# Chov2_led.net
KiCad netlist of a schematic drawn in Altium Designer
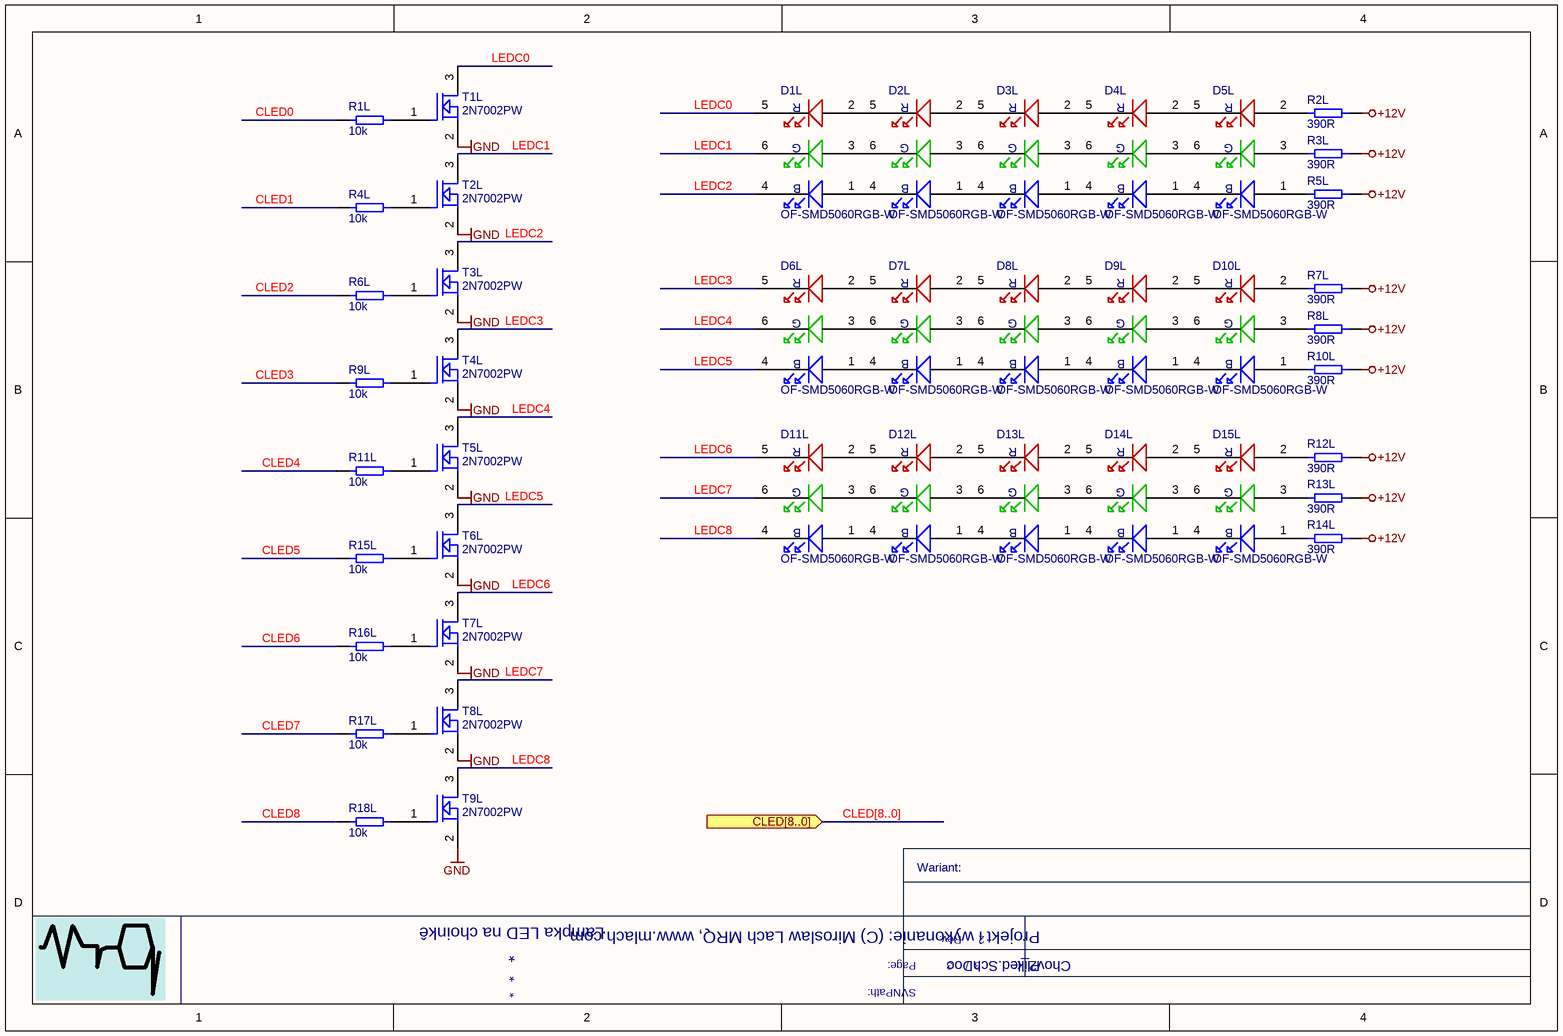
[diagram p0: Chov2_led.SchDoc]

(export (version "E")
  (design (tool "Eeschema 10.0.6"))
  (components
    (comp (ref "D1L")
      (value "OF-SMD5060RGB-W")
      (footprint "OF-SMD5060RGB-W")
      (libsource (lib "Parts") (part "OF-SMD5060RGB-W"))
    )
    (comp (ref "D2L")
      (value "OF-SMD5060RGB-W")
      (footprint "OF-SMD5060RGB-W")
      (libsource (lib "Parts") (part "OF-SMD5060RGB-W"))
    )
    (comp (ref "D3L")
      (value "OF-SMD5060RGB-W")
      (footprint "OF-SMD5060RGB-W")
      (libsource (lib "Parts") (part "OF-SMD5060RGB-W"))
    )
    (comp (ref "D4L")
      (value "OF-SMD5060RGB-W")
      (footprint "OF-SMD5060RGB-W")
      (libsource (lib "Parts") (part "OF-SMD5060RGB-W"))
    )
    (comp (ref "D5L")
      (value "OF-SMD5060RGB-W")
      (footprint "OF-SMD5060RGB-W")
      (libsource (lib "Parts") (part "OF-SMD5060RGB-W"))
    )
    (comp (ref "D6L")
      (value "OF-SMD5060RGB-W")
      (footprint "OF-SMD5060RGB-W")
      (libsource (lib "Parts") (part "OF-SMD5060RGB-W"))
    )
    (comp (ref "D7L")
      (value "OF-SMD5060RGB-W")
      (footprint "OF-SMD5060RGB-W")
      (libsource (lib "Parts") (part "OF-SMD5060RGB-W"))
    )
    (comp (ref "D8L")
      (value "OF-SMD5060RGB-W")
      (footprint "OF-SMD5060RGB-W")
      (libsource (lib "Parts") (part "OF-SMD5060RGB-W"))
    )
    (comp (ref "D9L")
      (value "OF-SMD5060RGB-W")
      (footprint "OF-SMD5060RGB-W")
      (libsource (lib "Parts") (part "OF-SMD5060RGB-W"))
    )
    (comp (ref "D10L")
      (value "OF-SMD5060RGB-W")
      (footprint "OF-SMD5060RGB-W")
      (libsource (lib "Parts") (part "OF-SMD5060RGB-W"))
    )
    (comp (ref "D11L")
      (value "OF-SMD5060RGB-W")
      (footprint "OF-SMD5060RGB-W")
      (libsource (lib "Parts") (part "OF-SMD5060RGB-W"))
    )
    (comp (ref "D12L")
      (value "OF-SMD5060RGB-W")
      (footprint "OF-SMD5060RGB-W")
      (libsource (lib "Parts") (part "OF-SMD5060RGB-W"))
    )
    (comp (ref "D13L")
      (value "OF-SMD5060RGB-W")
      (footprint "OF-SMD5060RGB-W")
      (libsource (lib "Parts") (part "OF-SMD5060RGB-W"))
    )
    (comp (ref "D14L")
      (value "OF-SMD5060RGB-W")
      (footprint "OF-SMD5060RGB-W")
      (libsource (lib "Parts") (part "OF-SMD5060RGB-W"))
    )
    (comp (ref "D15L")
      (value "OF-SMD5060RGB-W")
      (footprint "OF-SMD5060RGB-W")
      (libsource (lib "Parts") (part "OF-SMD5060RGB-W"))
    )
    (comp (ref "R1L")
      (value "0603WGF10KT5E")
      (footprint "0603-IPC")
      (fields (field (name "OTHERPARAMS") "10k") (field (name "TOLERANCE") "1%"))
      (libsource (lib "Parts") (part "R"))
    )
    (comp (ref "R2L")
      (value "0805WAF 390R T5E")
      (footprint "0805")
      (fields (field (name "OTHERPARAMS") "390R") (field (name "TOLERANCE") "1%"))
      (libsource (lib "Parts") (part "R"))
    )
    (comp (ref "R3L")
      (value "0805WAF 390R T5E")
      (footprint "0805")
      (fields (field (name "OTHERPARAMS") "390R") (field (name "TOLERANCE") "1%"))
      (libsource (lib "Parts") (part "R"))
    )
    (comp (ref "R4L")
      (value "0603WGF10KT5E")
      (footprint "0603-IPC")
      (fields (field (name "OTHERPARAMS") "10k") (field (name "TOLERANCE") "1%"))
      (libsource (lib "Parts") (part "R"))
    )
    (comp (ref "R5L")
      (value "0805WAF 390R T5E")
      (footprint "0805")
      (fields (field (name "OTHERPARAMS") "390R") (field (name "TOLERANCE") "1%"))
      (libsource (lib "Parts") (part "R"))
    )
    (comp (ref "R6L")
      (value "0603WGF10KT5E")
      (footprint "0603-IPC")
      (fields (field (name "OTHERPARAMS") "10k") (field (name "TOLERANCE") "1%"))
      (libsource (lib "Parts") (part "R"))
    )
    (comp (ref "R7L")
      (value "0805WAF 390R T5E")
      (footprint "0805")
      (fields (field (name "OTHERPARAMS") "390R") (field (name "TOLERANCE") "1%"))
      (libsource (lib "Parts") (part "R"))
    )
    (comp (ref "R8L")
      (value "0805WAF 390R T5E")
      (footprint "0805")
      (fields (field (name "OTHERPARAMS") "390R") (field (name "TOLERANCE") "1%"))
      (libsource (lib "Parts") (part "R"))
    )
    (comp (ref "R9L")
      (value "0603WGF10KT5E")
      (footprint "0603-IPC")
      (fields (field (name "OTHERPARAMS") "10k") (field (name "TOLERANCE") "1%"))
      (libsource (lib "Parts") (part "R"))
    )
    (comp (ref "R10L")
      (value "0805WAF 390R T5E")
      (footprint "0805")
      (fields (field (name "OTHERPARAMS") "390R") (field (name "TOLERANCE") "1%"))
      (libsource (lib "Parts") (part "R"))
    )
    (comp (ref "R11L")
      (value "0603WGF10KT5E")
      (footprint "0603-IPC")
      (fields (field (name "OTHERPARAMS") "10k") (field (name "TOLERANCE") "1%"))
      (libsource (lib "Parts") (part "R"))
    )
    (comp (ref "R12L")
      (value "0805WAF 390R T5E")
      (footprint "0805")
      (fields (field (name "OTHERPARAMS") "390R") (field (name "TOLERANCE") "1%"))
      (libsource (lib "Parts") (part "R"))
    )
    (comp (ref "R13L")
      (value "0805WAF 390R T5E")
      (footprint "0805")
      (fields (field (name "OTHERPARAMS") "390R") (field (name "TOLERANCE") "1%"))
      (libsource (lib "Parts") (part "R"))
    )
    (comp (ref "R14L")
      (value "0805WAF 390R T5E")
      (footprint "0805")
      (fields (field (name "OTHERPARAMS") "390R") (field (name "TOLERANCE") "1%"))
      (libsource (lib "Parts") (part "R"))
    )
    (comp (ref "R15L")
      (value "0603WGF10KT5E")
      (footprint "0603-IPC")
      (fields (field (name "OTHERPARAMS") "10k") (field (name "TOLERANCE") "1%"))
      (libsource (lib "Parts") (part "R"))
    )
    (comp (ref "R16L")
      (value "0603WGF10KT5E")
      (footprint "0603-IPC")
      (fields (field (name "OTHERPARAMS") "10k") (field (name "TOLERANCE") "1%"))
      (libsource (lib "Parts") (part "R"))
    )
    (comp (ref "R17L")
      (value "0603WGF10KT5E")
      (footprint "0603-IPC")
      (fields (field (name "OTHERPARAMS") "10k") (field (name "TOLERANCE") "1%"))
      (libsource (lib "Parts") (part "R"))
    )
    (comp (ref "R18L")
      (value "0603WGF10KT5E")
      (footprint "0603-IPC")
      (fields (field (name "OTHERPARAMS") "10k") (field (name "TOLERANCE") "1%"))
      (libsource (lib "Parts") (part "R"))
    )
    (comp (ref "T1L")
      (value "2N7002PW")
      (footprint "SOT323-3_FLOW")
      (libsource (lib "Parts") (part "MOSFET_N_SOT23-3"))
    )
    (comp (ref "T2L")
      (value "2N7002PW")
      (footprint "SOT323-3_FLOW")
      (libsource (lib "Parts") (part "MOSFET_N_SOT23-3"))
    )
    (comp (ref "T3L")
      (value "2N7002PW")
      (footprint "SOT323-3_FLOW")
      (libsource (lib "Parts") (part "MOSFET_N_SOT23-3"))
    )
    (comp (ref "T4L")
      (value "2N7002PW")
      (footprint "SOT323-3_FLOW")
      (libsource (lib "Parts") (part "MOSFET_N_SOT23-3"))
    )
    (comp (ref "T5L")
      (value "2N7002PW")
      (footprint "SOT323-3_FLOW")
      (libsource (lib "Parts") (part "MOSFET_N_SOT23-3"))
    )
    (comp (ref "T6L")
      (value "2N7002PW")
      (footprint "SOT323-3_FLOW")
      (libsource (lib "Parts") (part "MOSFET_N_SOT23-3"))
    )
    (comp (ref "T7L")
      (value "2N7002PW")
      (footprint "SOT323-3_FLOW")
      (libsource (lib "Parts") (part "MOSFET_N_SOT23-3"))
    )
    (comp (ref "T8L")
      (value "2N7002PW")
      (footprint "SOT323-3_FLOW")
      (libsource (lib "Parts") (part "MOSFET_N_SOT23-3"))
    )
    (comp (ref "T9L")
      (value "2N7002PW")
      (footprint "SOT323-3_FLOW")
      (libsource (lib "Parts") (part "MOSFET_N_SOT23-3"))
    )
  )
  (nets
    (net (code "1") (name "+12V") (class "Default")
      (node (ref "R10L") (pin "2") (pinfunction "2_2") (pintype "passive"))
      (node (ref "R12L") (pin "2") (pinfunction "2_2") (pintype "passive"))
      (node (ref "R13L") (pin "2") (pinfunction "2_2") (pintype "passive"))
      (node (ref "R14L") (pin "2") (pinfunction "2_2") (pintype "passive"))
      (node (ref "R2L") (pin "2") (pinfunction "2_2") (pintype "passive"))
      (node (ref "R3L") (pin "2") (pinfunction "2_2") (pintype "passive"))
      (node (ref "R5L") (pin "2") (pinfunction "2_2") (pintype "passive"))
      (node (ref "R7L") (pin "2") (pinfunction "2_2") (pintype "passive"))
      (node (ref "R8L") (pin "2") (pinfunction "2_2") (pintype "passive"))
    )
    (net (code "2") (name "/CLED0") (class "Default")
      (node (ref "R1L") (pin "1") (pinfunction "1_1") (pintype "passive"))
    )
    (net (code "3") (name "/CLED1") (class "Default")
      (node (ref "R4L") (pin "1") (pinfunction "1_1") (pintype "passive"))
    )
    (net (code "4") (name "/CLED2") (class "Default")
      (node (ref "R6L") (pin "1") (pinfunction "1_1") (pintype "passive"))
    )
    (net (code "5") (name "/CLED3") (class "Default")
      (node (ref "R9L") (pin "1") (pinfunction "1_1") (pintype "passive"))
    )
    (net (code "6") (name "/CLED4") (class "Default")
      (node (ref "R11L") (pin "1") (pinfunction "1_1") (pintype "passive"))
    )
    (net (code "7") (name "/CLED5") (class "Default")
      (node (ref "R15L") (pin "1") (pinfunction "1_1") (pintype "passive"))
    )
    (net (code "8") (name "/CLED6") (class "Default")
      (node (ref "R16L") (pin "1") (pinfunction "1_1") (pintype "passive"))
    )
    (net (code "9") (name "/CLED7") (class "Default")
      (node (ref "R17L") (pin "1") (pinfunction "1_1") (pintype "passive"))
    )
    (net (code "10") (name "/CLED8") (class "Default")
      (node (ref "R18L") (pin "1") (pinfunction "1_1") (pintype "passive"))
    )
    (net (code "12") (name "/LEDC0") (class "Default")
      (node (ref "D1L") (pin "5") (pinfunction "CATH_5") (pintype "passive"))
      (node (ref "T1L") (pin "3") (pinfunction "DRAIN_3") (pintype "passive"))
    )
    (net (code "13") (name "/LEDC1") (class "Default")
      (node (ref "D1L") (pin "6") (pinfunction "CATH_6") (pintype "passive"))
      (node (ref "T2L") (pin "3") (pinfunction "DRAIN_3") (pintype "passive"))
    )
    (net (code "14") (name "/LEDC2") (class "Default")
      (node (ref "D1L") (pin "4") (pinfunction "CATH_4") (pintype "passive"))
      (node (ref "T3L") (pin "3") (pinfunction "DRAIN_3") (pintype "passive"))
    )
    (net (code "15") (name "/LEDC3") (class "Default")
      (node (ref "D6L") (pin "5") (pinfunction "CATH_5") (pintype "passive"))
      (node (ref "T4L") (pin "3") (pinfunction "DRAIN_3") (pintype "passive"))
    )
    (net (code "16") (name "/LEDC4") (class "Default")
      (node (ref "D6L") (pin "6") (pinfunction "CATH_6") (pintype "passive"))
      (node (ref "T5L") (pin "3") (pinfunction "DRAIN_3") (pintype "passive"))
    )
    (net (code "17") (name "/LEDC5") (class "Default")
      (node (ref "D6L") (pin "4") (pinfunction "CATH_4") (pintype "passive"))
      (node (ref "T6L") (pin "3") (pinfunction "DRAIN_3") (pintype "passive"))
    )
    (net (code "18") (name "/LEDC6") (class "Default")
      (node (ref "D11L") (pin "5") (pinfunction "CATH_5") (pintype "passive"))
      (node (ref "T7L") (pin "3") (pinfunction "DRAIN_3") (pintype "passive"))
    )
    (net (code "19") (name "/LEDC7") (class "Default")
      (node (ref "D11L") (pin "6") (pinfunction "CATH_6") (pintype "passive"))
      (node (ref "T8L") (pin "3") (pinfunction "DRAIN_3") (pintype "passive"))
    )
    (net (code "20") (name "/LEDC8") (class "Default")
      (node (ref "D11L") (pin "4") (pinfunction "CATH_4") (pintype "passive"))
      (node (ref "T9L") (pin "3") (pinfunction "DRAIN_3") (pintype "passive"))
    )
    (net (code "21") (name "GND") (class "Default")
      (node (ref "T1L") (pin "2") (pinfunction "SOURCE_2") (pintype "passive"))
      (node (ref "T2L") (pin "2") (pinfunction "SOURCE_2") (pintype "passive"))
      (node (ref "T3L") (pin "2") (pinfunction "SOURCE_2") (pintype "passive"))
      (node (ref "T4L") (pin "2") (pinfunction "SOURCE_2") (pintype "passive"))
      (node (ref "T5L") (pin "2") (pinfunction "SOURCE_2") (pintype "passive"))
      (node (ref "T6L") (pin "2") (pinfunction "SOURCE_2") (pintype "passive"))
      (node (ref "T7L") (pin "2") (pinfunction "SOURCE_2") (pintype "passive"))
      (node (ref "T8L") (pin "2") (pinfunction "SOURCE_2") (pintype "passive"))
      (node (ref "T9L") (pin "2") (pinfunction "SOURCE_2") (pintype "passive"))
    )
    (net (code "22") (name "Net-(D1L-ANOD-Pad1)") (class "Default")
      (node (ref "D1L") (pin "1") (pinfunction "ANOD_1") (pintype "passive"))
      (node (ref "D2L") (pin "4") (pinfunction "CATH_4") (pintype "passive"))
    )
    (net (code "23") (name "Net-(D1L-ANOD-Pad2)") (class "Default")
      (node (ref "D1L") (pin "2") (pinfunction "ANOD_2") (pintype "passive"))
      (node (ref "D2L") (pin "5") (pinfunction "CATH_5") (pintype "passive"))
    )
    (net (code "24") (name "Net-(D1L-ANOD-Pad3)") (class "Default")
      (node (ref "D1L") (pin "3") (pinfunction "ANOD_3") (pintype "passive"))
      (node (ref "D2L") (pin "6") (pinfunction "CATH_6") (pintype "passive"))
    )
    (net (code "25") (name "Net-(D2L-ANOD-Pad1)") (class "Default")
      (node (ref "D2L") (pin "1") (pinfunction "ANOD_1") (pintype "passive"))
      (node (ref "D3L") (pin "4") (pinfunction "CATH_4") (pintype "passive"))
    )
    (net (code "26") (name "Net-(D2L-ANOD-Pad2)") (class "Default")
      (node (ref "D2L") (pin "2") (pinfunction "ANOD_2") (pintype "passive"))
      (node (ref "D3L") (pin "5") (pinfunction "CATH_5") (pintype "passive"))
    )
    (net (code "27") (name "Net-(D2L-ANOD-Pad3)") (class "Default")
      (node (ref "D2L") (pin "3") (pinfunction "ANOD_3") (pintype "passive"))
      (node (ref "D3L") (pin "6") (pinfunction "CATH_6") (pintype "passive"))
    )
    (net (code "28") (name "Net-(D3L-ANOD-Pad1)") (class "Default")
      (node (ref "D3L") (pin "1") (pinfunction "ANOD_1") (pintype "passive"))
      (node (ref "D4L") (pin "4") (pinfunction "CATH_4") (pintype "passive"))
    )
    (net (code "29") (name "Net-(D3L-ANOD-Pad2)") (class "Default")
      (node (ref "D3L") (pin "2") (pinfunction "ANOD_2") (pintype "passive"))
      (node (ref "D4L") (pin "5") (pinfunction "CATH_5") (pintype "passive"))
    )
    (net (code "30") (name "Net-(D3L-ANOD-Pad3)") (class "Default")
      (node (ref "D3L") (pin "3") (pinfunction "ANOD_3") (pintype "passive"))
      (node (ref "D4L") (pin "6") (pinfunction "CATH_6") (pintype "passive"))
    )
    (net (code "31") (name "Net-(D4L-ANOD-Pad1)") (class "Default")
      (node (ref "D4L") (pin "1") (pinfunction "ANOD_1") (pintype "passive"))
      (node (ref "D5L") (pin "4") (pinfunction "CATH_4") (pintype "passive"))
    )
    (net (code "32") (name "Net-(D4L-ANOD-Pad2)") (class "Default")
      (node (ref "D4L") (pin "2") (pinfunction "ANOD_2") (pintype "passive"))
      (node (ref "D5L") (pin "5") (pinfunction "CATH_5") (pintype "passive"))
    )
    (net (code "33") (name "Net-(D4L-ANOD-Pad3)") (class "Default")
      (node (ref "D4L") (pin "3") (pinfunction "ANOD_3") (pintype "passive"))
      (node (ref "D5L") (pin "6") (pinfunction "CATH_6") (pintype "passive"))
    )
    (net (code "34") (name "Net-(D5L-ANOD-Pad1)") (class "Default")
      (node (ref "D5L") (pin "1") (pinfunction "ANOD_1") (pintype "passive"))
      (node (ref "R5L") (pin "1") (pinfunction "1_1") (pintype "passive"))
    )
    (net (code "35") (name "Net-(D5L-ANOD-Pad2)") (class "Default")
      (node (ref "D5L") (pin "2") (pinfunction "ANOD_2") (pintype "passive"))
      (node (ref "R2L") (pin "1") (pinfunction "1_1") (pintype "passive"))
    )
    (net (code "36") (name "Net-(D5L-ANOD-Pad3)") (class "Default")
      (node (ref "D5L") (pin "3") (pinfunction "ANOD_3") (pintype "passive"))
      (node (ref "R3L") (pin "1") (pinfunction "1_1") (pintype "passive"))
    )
    (net (code "37") (name "Net-(D6L-ANOD-Pad1)") (class "Default")
      (node (ref "D6L") (pin "1") (pinfunction "ANOD_1") (pintype "passive"))
      (node (ref "D7L") (pin "4") (pinfunction "CATH_4") (pintype "passive"))
    )
    (net (code "38") (name "Net-(D6L-ANOD-Pad2)") (class "Default")
      (node (ref "D6L") (pin "2") (pinfunction "ANOD_2") (pintype "passive"))
      (node (ref "D7L") (pin "5") (pinfunction "CATH_5") (pintype "passive"))
    )
    (net (code "39") (name "Net-(D6L-ANOD-Pad3)") (class "Default")
      (node (ref "D6L") (pin "3") (pinfunction "ANOD_3") (pintype "passive"))
      (node (ref "D7L") (pin "6") (pinfunction "CATH_6") (pintype "passive"))
    )
    (net (code "40") (name "Net-(D7L-ANOD-Pad1)") (class "Default")
      (node (ref "D7L") (pin "1") (pinfunction "ANOD_1") (pintype "passive"))
      (node (ref "D8L") (pin "4") (pinfunction "CATH_4") (pintype "passive"))
    )
    (net (code "41") (name "Net-(D7L-ANOD-Pad2)") (class "Default")
      (node (ref "D7L") (pin "2") (pinfunction "ANOD_2") (pintype "passive"))
      (node (ref "D8L") (pin "5") (pinfunction "CATH_5") (pintype "passive"))
    )
    (net (code "42") (name "Net-(D7L-ANOD-Pad3)") (class "Default")
      (node (ref "D7L") (pin "3") (pinfunction "ANOD_3") (pintype "passive"))
      (node (ref "D8L") (pin "6") (pinfunction "CATH_6") (pintype "passive"))
    )
    (net (code "43") (name "Net-(D8L-ANOD-Pad1)") (class "Default")
      (node (ref "D8L") (pin "1") (pinfunction "ANOD_1") (pintype "passive"))
      (node (ref "D9L") (pin "4") (pinfunction "CATH_4") (pintype "passive"))
    )
    (net (code "44") (name "Net-(D8L-ANOD-Pad2)") (class "Default")
      (node (ref "D8L") (pin "2") (pinfunction "ANOD_2") (pintype "passive"))
      (node (ref "D9L") (pin "5") (pinfunction "CATH_5") (pintype "passive"))
    )
    (net (code "45") (name "Net-(D8L-ANOD-Pad3)") (class "Default")
      (node (ref "D8L") (pin "3") (pinfunction "ANOD_3") (pintype "passive"))
      (node (ref "D9L") (pin "6") (pinfunction "CATH_6") (pintype "passive"))
    )
    (net (code "46") (name "Net-(D10L-ANOD-Pad1)") (class "Default")
      (node (ref "D10L") (pin "1") (pinfunction "ANOD_1") (pintype "passive"))
      (node (ref "R10L") (pin "1") (pinfunction "1_1") (pintype "passive"))
    )
    (net (code "47") (name "Net-(D10L-ANOD-Pad2)") (class "Default")
      (node (ref "D10L") (pin "2") (pinfunction "ANOD_2") (pintype "passive"))
      (node (ref "R7L") (pin "1") (pinfunction "1_1") (pintype "passive"))
    )
    (net (code "48") (name "Net-(D10L-ANOD-Pad3)") (class "Default")
      (node (ref "D10L") (pin "3") (pinfunction "ANOD_3") (pintype "passive"))
      (node (ref "R8L") (pin "1") (pinfunction "1_1") (pintype "passive"))
    )
    (net (code "49") (name "Net-(D10L-CATH-Pad4)") (class "Default")
      (node (ref "D10L") (pin "4") (pinfunction "CATH_4") (pintype "passive"))
      (node (ref "D9L") (pin "1") (pinfunction "ANOD_1") (pintype "passive"))
    )
    (net (code "50") (name "Net-(D10L-CATH-Pad5)") (class "Default")
      (node (ref "D10L") (pin "5") (pinfunction "CATH_5") (pintype "passive"))
      (node (ref "D9L") (pin "2") (pinfunction "ANOD_2") (pintype "passive"))
    )
    (net (code "51") (name "Net-(D10L-CATH-Pad6)") (class "Default")
      (node (ref "D10L") (pin "6") (pinfunction "CATH_6") (pintype "passive"))
      (node (ref "D9L") (pin "3") (pinfunction "ANOD_3") (pintype "passive"))
    )
    (net (code "52") (name "Net-(D11L-ANOD-Pad1)") (class "Default")
      (node (ref "D11L") (pin "1") (pinfunction "ANOD_1") (pintype "passive"))
      (node (ref "D12L") (pin "4") (pinfunction "CATH_4") (pintype "passive"))
    )
    (net (code "53") (name "Net-(D11L-ANOD-Pad2)") (class "Default")
      (node (ref "D11L") (pin "2") (pinfunction "ANOD_2") (pintype "passive"))
      (node (ref "D12L") (pin "5") (pinfunction "CATH_5") (pintype "passive"))
    )
    (net (code "54") (name "Net-(D11L-ANOD-Pad3)") (class "Default")
      (node (ref "D11L") (pin "3") (pinfunction "ANOD_3") (pintype "passive"))
      (node (ref "D12L") (pin "6") (pinfunction "CATH_6") (pintype "passive"))
    )
    (net (code "55") (name "Net-(D12L-ANOD-Pad1)") (class "Default")
      (node (ref "D12L") (pin "1") (pinfunction "ANOD_1") (pintype "passive"))
      (node (ref "D13L") (pin "4") (pinfunction "CATH_4") (pintype "passive"))
    )
    (net (code "56") (name "Net-(D12L-ANOD-Pad2)") (class "Default")
      (node (ref "D12L") (pin "2") (pinfunction "ANOD_2") (pintype "passive"))
      (node (ref "D13L") (pin "5") (pinfunction "CATH_5") (pintype "passive"))
    )
    (net (code "57") (name "Net-(D12L-ANOD-Pad3)") (class "Default")
      (node (ref "D12L") (pin "3") (pinfunction "ANOD_3") (pintype "passive"))
      (node (ref "D13L") (pin "6") (pinfunction "CATH_6") (pintype "passive"))
    )
    (net (code "58") (name "Net-(D13L-ANOD-Pad1)") (class "Default")
      (node (ref "D13L") (pin "1") (pinfunction "ANOD_1") (pintype "passive"))
      (node (ref "D14L") (pin "4") (pinfunction "CATH_4") (pintype "passive"))
    )
    (net (code "59") (name "Net-(D13L-ANOD-Pad2)") (class "Default")
      (node (ref "D13L") (pin "2") (pinfunction "ANOD_2") (pintype "passive"))
      (node (ref "D14L") (pin "5") (pinfunction "CATH_5") (pintype "passive"))
    )
    (net (code "60") (name "Net-(D13L-ANOD-Pad3)") (class "Default")
      (node (ref "D13L") (pin "3") (pinfunction "ANOD_3") (pintype "passive"))
      (node (ref "D14L") (pin "6") (pinfunction "CATH_6") (pintype "passive"))
    )
    (net (code "61") (name "Net-(D14L-ANOD-Pad1)") (class "Default")
      (node (ref "D14L") (pin "1") (pinfunction "ANOD_1") (pintype "passive"))
      (node (ref "D15L") (pin "4") (pinfunction "CATH_4") (pintype "passive"))
    )
    (net (code "62") (name "Net-(D14L-ANOD-Pad2)") (class "Default")
      (node (ref "D14L") (pin "2") (pinfunction "ANOD_2") (pintype "passive"))
      (node (ref "D15L") (pin "5") (pinfunction "CATH_5") (pintype "passive"))
    )
    (net (code "63") (name "Net-(D14L-ANOD-Pad3)") (class "Default")
      (node (ref "D14L") (pin "3") (pinfunction "ANOD_3") (pintype "passive"))
      (node (ref "D15L") (pin "6") (pinfunction "CATH_6") (pintype "passive"))
    )
    (net (code "64") (name "Net-(D15L-ANOD-Pad1)") (class "Default")
      (node (ref "D15L") (pin "1") (pinfunction "ANOD_1") (pintype "passive"))
      (node (ref "R14L") (pin "1") (pinfunction "1_1") (pintype "passive"))
    )
    (net (code "65") (name "Net-(D15L-ANOD-Pad2)") (class "Default")
      (node (ref "D15L") (pin "2") (pinfunction "ANOD_2") (pintype "passive"))
      (node (ref "R12L") (pin "1") (pinfunction "1_1") (pintype "passive"))
    )
    (net (code "66") (name "Net-(D15L-ANOD-Pad3)") (class "Default")
      (node (ref "D15L") (pin "3") (pinfunction "ANOD_3") (pintype "passive"))
      (node (ref "R13L") (pin "1") (pinfunction "1_1") (pintype "passive"))
    )
    (net (code "67") (name "Net-(T1L-GATE)") (class "Default")
      (node (ref "R1L") (pin "2") (pinfunction "2_2") (pintype "passive"))
      (node (ref "T1L") (pin "1") (pinfunction "GATE_1") (pintype "passive"))
    )
    (net (code "68") (name "Net-(T2L-GATE)") (class "Default")
      (node (ref "R4L") (pin "2") (pinfunction "2_2") (pintype "passive"))
      (node (ref "T2L") (pin "1") (pinfunction "GATE_1") (pintype "passive"))
    )
    (net (code "69") (name "Net-(T3L-GATE)") (class "Default")
      (node (ref "R6L") (pin "2") (pinfunction "2_2") (pintype "passive"))
      (node (ref "T3L") (pin "1") (pinfunction "GATE_1") (pintype "passive"))
    )
    (net (code "70") (name "Net-(T4L-GATE)") (class "Default")
      (node (ref "R9L") (pin "2") (pinfunction "2_2") (pintype "passive"))
      (node (ref "T4L") (pin "1") (pinfunction "GATE_1") (pintype "passive"))
    )
    (net (code "71") (name "Net-(T5L-GATE)") (class "Default")
      (node (ref "R11L") (pin "2") (pinfunction "2_2") (pintype "passive"))
      (node (ref "T5L") (pin "1") (pinfunction "GATE_1") (pintype "passive"))
    )
    (net (code "72") (name "Net-(T6L-GATE)") (class "Default")
      (node (ref "R15L") (pin "2") (pinfunction "2_2") (pintype "passive"))
      (node (ref "T6L") (pin "1") (pinfunction "GATE_1") (pintype "passive"))
    )
    (net (code "73") (name "Net-(T7L-GATE)") (class "Default")
      (node (ref "R16L") (pin "2") (pinfunction "2_2") (pintype "passive"))
      (node (ref "T7L") (pin "1") (pinfunction "GATE_1") (pintype "passive"))
    )
    (net (code "74") (name "Net-(T8L-GATE)") (class "Default")
      (node (ref "R17L") (pin "2") (pinfunction "2_2") (pintype "passive"))
      (node (ref "T8L") (pin "1") (pinfunction "GATE_1") (pintype "passive"))
    )
    (net (code "75") (name "Net-(T9L-GATE)") (class "Default")
      (node (ref "R18L") (pin "2") (pinfunction "2_2") (pintype "passive"))
      (node (ref "T9L") (pin "1") (pinfunction "GATE_1") (pintype "passive"))
    )
  )
)
